# KEY_V0_01_160620.net
KiCad netlist of a schematic drawn in Altium Designer
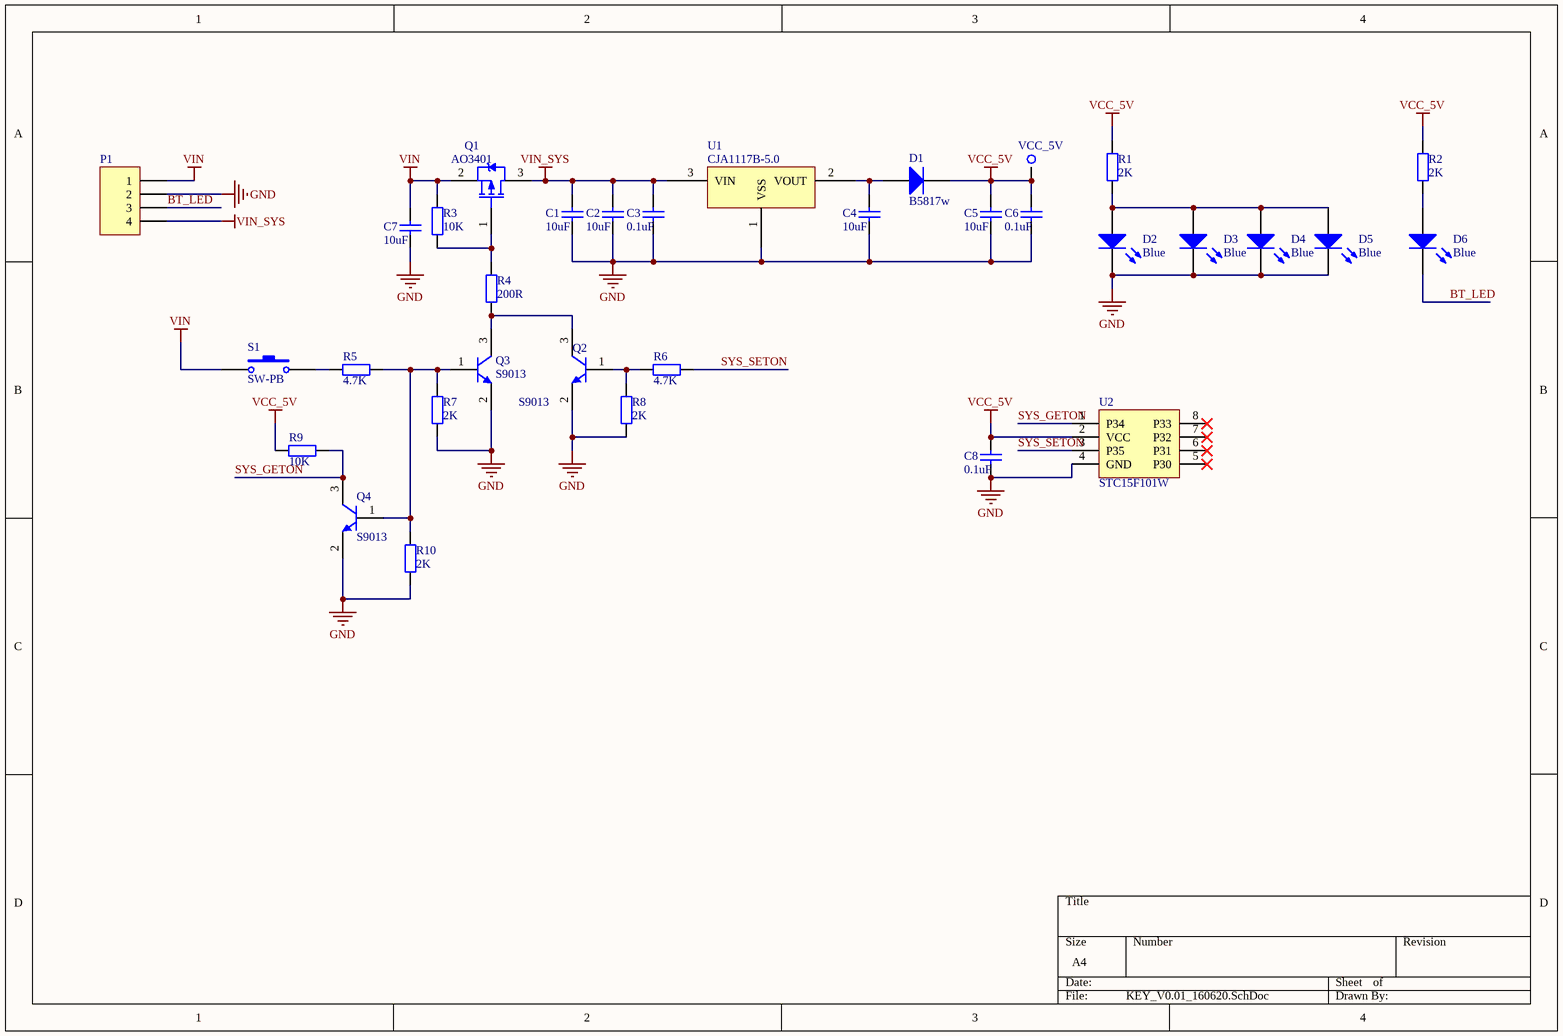
[diagram p0: KEY_V0.01_160620.SchDoc]

(export (version "E")
  (design (tool "Eeschema 10.0.6"))
  (components
    (comp (ref "C1")
      (value "10uF")
      (footprint "C0603")
      (description "三星 10uF 10% 16V C0603 X5R")
      (libsource (lib "Miscellaneous Devices") (part "Cap"))
    )
    (comp (ref "C2")
      (value "10uF")
      (footprint "C0603")
      (description "三星 10uF 10% 16V C0603 X5R")
      (libsource (lib "Miscellaneous Devices") (part "Cap"))
    )
    (comp (ref "C3")
      (value "0.1uF")
      (footprint "C0603")
      (description "三星 100nF 10% 25V C0603 X7R")
      (libsource (lib "Miscellaneous Devices") (part "Cap"))
    )
    (comp (ref "C4")
      (value "10uF")
      (footprint "C0603")
      (description "三星 10uF 10% 16V C0603 X5R")
      (libsource (lib "Miscellaneous Devices") (part "Cap"))
    )
    (comp (ref "C5")
      (value "10uF")
      (footprint "C0603")
      (description "三星 10uF 10% 16V C0603 X5R")
      (libsource (lib "Miscellaneous Devices") (part "Cap"))
    )
    (comp (ref "C6")
      (value "0.1uF")
      (footprint "C0603")
      (description "三星 100nF 10% 25V C0603 X7R")
      (libsource (lib "Miscellaneous Devices") (part "Cap"))
    )
    (comp (ref "C7")
      (value "10uF")
      (footprint "C0603")
      (description "三星 10uF 10% 16V C0603 X5R")
      (libsource (lib "Miscellaneous Devices") (part "Cap"))
    )
    (comp (ref "C8")
      (value "0.1uF")
      (footprint "C0603")
      (description "三星 100nF 10% 25V C0603 X7R")
      (libsource (lib "Miscellaneous Devices") (part "Cap"))
    )
    (comp (ref "D1")
      (value "B5817w")
      (footprint "SOD-123")
      (description "长电 B5817W SOD-123")
      (libsource (lib "Miscellaneous Devices") (part "Diode 1N4002"))
    )
    (comp (ref "D2")
      (value "Blue")
      (footprint "D0603")
      (description "蓝箭 蓝灯高亮 0603 Blue-LED")
      (libsource (lib "Miscellaneous Devices") (part "LED0"))
    )
    (comp (ref "D3")
      (value "Blue")
      (footprint "D0603")
      (description "蓝箭 蓝灯高亮 0603 Blue-LED")
      (libsource (lib "Miscellaneous Devices") (part "LED0"))
    )
    (comp (ref "D4")
      (value "Blue")
      (footprint "D0603")
      (description "蓝箭 蓝灯高亮 0603 Blue-LED")
      (libsource (lib "Miscellaneous Devices") (part "LED0"))
    )
    (comp (ref "D5")
      (value "Blue")
      (footprint "D0603")
      (description "蓝箭 蓝灯高亮 0603 Blue-LED")
      (libsource (lib "Miscellaneous Devices") (part "LED0"))
    )
    (comp (ref "D6")
      (value "Blue")
      (footprint "D0603")
      (description "蓝箭 蓝灯高亮 0603 Blue-LED")
      (libsource (lib "Miscellaneous Devices") (part "LED0"))
    )
    (comp (ref "P1")
      (value "Download_pad")
      (footprint "HEADER1X4/2.0MM_1")
      (description "AMP（国产仿制） AMP2.0mm-4Pin（板端） 间距2.00mm 卧插式 白色")
      (libsource (lib "Miscellaneous Connectors") (part "Header 4"))
    )
    (comp (ref "Q1") (value "AO3401") (footprint "SOT-23-3") (libsource (lib "makeblock") (part "PMOS")))
    (comp (ref "Q2") (value "S9013") (footprint "SOT-23") (libsource (lib "makeblock") (part "NPN_SMT")))
    (comp (ref "Q3") (value "S9013") (footprint "SOT-23") (libsource (lib "makeblock") (part "NPN_SMT")))
    (comp (ref "Q4") (value "S9013") (footprint "SOT-23") (libsource (lib "makeblock") (part "NPN_SMT")))
    (comp (ref "R1")
      (value "2K")
      (footprint "R0603")
      (description "国巨 2K 1% R0603")
      (libsource (lib "Miscellaneous Devices") (part "Res2"))
    )
    (comp (ref "R2")
      (value "2K")
      (footprint "R0603")
      (description "国巨 2K 1% R0603")
      (libsource (lib "") (part "Res2_2"))
    )
    (comp (ref "R3")
      (value "10K")
      (footprint "R0603")
      (description "国巨 10K 1% R0603")
      (libsource (lib "Miscellaneous Devices") (part "Res2"))
    )
    (comp (ref "R4")
      (value "200R")
      (footprint "R0603")
      (description "国巨 200R 1% R0603")
      (libsource (lib "Miscellaneous Devices") (part "Res2"))
    )
    (comp (ref "R5")
      (value "4.7K")
      (footprint "R0603")
      (description "国巨 4.7K 1% R0603")
      (libsource (lib "") (part "Res2_1"))
    )
    (comp (ref "R6")
      (value "4.7K")
      (footprint "R0603")
      (description "国巨 4.7K 1% R0603")
      (libsource (lib "") (part "Res2_1"))
    )
    (comp (ref "R7")
      (value "2K")
      (footprint "R0603")
      (description "国巨 2K 1% R0603")
      (libsource (lib "Miscellaneous Devices") (part "Res2"))
    )
    (comp (ref "R8")
      (value "2K")
      (footprint "R0603")
      (description "国巨 2K 1% R0603")
      (libsource (lib "Miscellaneous Devices") (part "Res2"))
    )
    (comp (ref "R9")
      (value "10K")
      (footprint "R0603")
      (description "国巨 10K 1% R0603")
      (libsource (lib "") (part "Res2_1"))
    )
    (comp (ref "R10")
      (value "2K")
      (footprint "R0603")
      (description "国巨 2K 1% R0603")
      (libsource (lib "Miscellaneous Devices") (part "Res2"))
    )
    (comp (ref "S1")
      (value "SW-PB")
      (footprint "SW-TS-021")
      (description "登鼎 3mm*6mm*2.5mm（长*宽*高） 贴片 白色按钮")
      (libsource (lib "Miscellaneous Devices") (part "SW-PB"))
    )
    (comp (ref "U1")
      (value "CJA1117B-5.0")
      (footprint "SOT-89-3L")
      (description "长电 三端稳压芯片 CJA1117B-3.3 3.3V 1A SOT-89-3L")
      (libsource (lib "Mylib") (part "XC6206"))
    )
    (comp (ref "U2")
      (value "STC15F101W")
      (footprint "SOP-8N")
      (description "宏晶 MCU STC15F101W SOP-8")
      (libsource (lib "makeblocK") (part "STC15F101W"))
    )
    (comp (ref "VCC_5V")
      (value "*")
      (footprint "Testpoint 1mm")
      (description "Testpoint")
      (libsource (lib "makeblocK") (part "Testpoint"))
    )
  )
  (nets
    (net (code "1") (name "/BT_LED") (class "Default")
      (node (ref "D6") (pin "2") (pinfunction "K_2") (pintype "passive"))
      (node (ref "P1") (pin "3") (pinfunction "3_3") (pintype "passive"))
    )
    (net (code "2") (name "/SYS_GETON") (class "Default")
      (node (ref "Q4") (pin "3") (pinfunction "C_3") (pintype "passive"))
      (node (ref "R9") (pin "1") (pinfunction "1_1") (pintype "passive"))
      (node (ref "U2") (pin "1") (pinfunction "P34_1") (pintype "passive"))
    )
    (net (code "3") (name "/SYS_SETON") (class "Default")
      (node (ref "R6") (pin "1") (pinfunction "1_1") (pintype "passive"))
      (node (ref "U2") (pin "3") (pinfunction "P35_3") (pintype "passive"))
    )
    (net (code "4") (name "GND") (class "Default")
      (node (ref "C1") (pin "2") (pinfunction "2_2") (pintype "passive"))
      (node (ref "C2") (pin "2") (pinfunction "2_2") (pintype "passive"))
      (node (ref "C3") (pin "2") (pinfunction "2_2") (pintype "passive"))
      (node (ref "C4") (pin "2") (pinfunction "2_2") (pintype "passive"))
      (node (ref "C5") (pin "2") (pinfunction "2_2") (pintype "passive"))
      (node (ref "C6") (pin "2") (pinfunction "2_2") (pintype "passive"))
      (node (ref "C7") (pin "2") (pinfunction "2_2") (pintype "passive"))
      (node (ref "C8") (pin "2") (pinfunction "2_2") (pintype "passive"))
      (node (ref "D2") (pin "2") (pinfunction "K_2") (pintype "passive"))
      (node (ref "D3") (pin "2") (pinfunction "K_2") (pintype "passive"))
      (node (ref "D4") (pin "2") (pinfunction "K_2") (pintype "passive"))
      (node (ref "D5") (pin "2") (pinfunction "K_2") (pintype "passive"))
      (node (ref "P1") (pin "2") (pinfunction "2_2") (pintype "passive"))
      (node (ref "Q2") (pin "2") (pinfunction "E_2") (pintype "passive"))
      (node (ref "Q3") (pin "2") (pinfunction "E_2") (pintype "passive"))
      (node (ref "Q4") (pin "2") (pinfunction "E_2") (pintype "passive"))
      (node (ref "R10") (pin "1") (pinfunction "1_1") (pintype "passive"))
      (node (ref "R7") (pin "1") (pinfunction "1_1") (pintype "passive"))
      (node (ref "R8") (pin "1") (pinfunction "1_1") (pintype "passive"))
      (node (ref "U1") (pin "1") (pinfunction "VSS_1") (pintype "passive"))
      (node (ref "U2") (pin "4") (pinfunction "GND_4") (pintype "passive"))
    )
    (net (code "5") (name "Net-(D1-A)") (class "Default")
      (node (ref "C4") (pin "1") (pinfunction "1_1") (pintype "passive"))
      (node (ref "D1") (pin "1") (pinfunction "A_1") (pintype "passive"))
      (node (ref "U1") (pin "2") (pinfunction "VOUT_2") (pintype "passive"))
    )
    (net (code "6") (name "Net-(D2-A)") (class "Default")
      (node (ref "D2") (pin "1") (pinfunction "A_1") (pintype "passive"))
      (node (ref "D3") (pin "1") (pinfunction "A_1") (pintype "passive"))
      (node (ref "D4") (pin "1") (pinfunction "A_1") (pintype "passive"))
      (node (ref "D5") (pin "1") (pinfunction "A_1") (pintype "passive"))
      (node (ref "R1") (pin "1") (pinfunction "1_1") (pintype "passive"))
    )
    (net (code "7") (name "Net-(D6-A)") (class "Default")
      (node (ref "D6") (pin "1") (pinfunction "A_1") (pintype "passive"))
      (node (ref "R2") (pin "2") (pinfunction "2_2") (pintype "passive"))
    )
    (net (code "8") (name "Net-(Q1-G)") (class "Default")
      (node (ref "Q1") (pin "1") (pinfunction "G_1") (pintype "passive"))
      (node (ref "R3") (pin "1") (pinfunction "1_1") (pintype "passive"))
      (node (ref "R4") (pin "2") (pinfunction "2_2") (pintype "passive"))
    )
    (net (code "9") (name "Net-(Q2-B)") (class "Default")
      (node (ref "Q2") (pin "1") (pinfunction "B_1") (pintype "passive"))
      (node (ref "R6") (pin "2") (pinfunction "2_2") (pintype "passive"))
      (node (ref "R8") (pin "2") (pinfunction "2_2") (pintype "passive"))
    )
    (net (code "10") (name "Net-(Q2-C)") (class "Default")
      (node (ref "Q2") (pin "3") (pinfunction "C_3") (pintype "passive"))
      (node (ref "Q3") (pin "3") (pinfunction "C_3") (pintype "passive"))
      (node (ref "R4") (pin "1") (pinfunction "1_1") (pintype "passive"))
    )
    (net (code "11") (name "Net-(Q3-B)") (class "Default")
      (node (ref "Q3") (pin "1") (pinfunction "B_1") (pintype "passive"))
      (node (ref "Q4") (pin "1") (pinfunction "B_1") (pintype "passive"))
      (node (ref "R10") (pin "2") (pinfunction "2_2") (pintype "passive"))
      (node (ref "R5") (pin "1") (pinfunction "1_1") (pintype "passive"))
      (node (ref "R7") (pin "2") (pinfunction "2_2") (pintype "passive"))
    )
    (net (code "12") (name "Net-(R5-Pad2)") (class "Default")
      (node (ref "R5") (pin "2") (pinfunction "2_2") (pintype "passive"))
      (node (ref "S1") (pin "2") (pinfunction "2_2") (pintype "passive"))
    )
    (net (code "13") (name "VCC_5V") (class "Default")
      (node (ref "C5") (pin "1") (pinfunction "1_1") (pintype "passive"))
      (node (ref "C6") (pin "1") (pinfunction "1_1") (pintype "passive"))
      (node (ref "C8") (pin "1") (pinfunction "1_1") (pintype "passive"))
      (node (ref "D1") (pin "2") (pinfunction "K_2") (pintype "passive"))
      (node (ref "R1") (pin "2") (pinfunction "2_2") (pintype "passive"))
      (node (ref "R2") (pin "1") (pinfunction "1_1") (pintype "passive"))
      (node (ref "R9") (pin "2") (pinfunction "2_2") (pintype "passive"))
      (node (ref "U2") (pin "2") (pinfunction "VCC_2") (pintype "passive"))
      (node (ref "VCC_5V") (pin "1") (pinfunction "1_1") (pintype "passive"))
    )
    (net (code "14") (name "VIN") (class "Default")
      (node (ref "C7") (pin "1") (pinfunction "1_1") (pintype "passive"))
      (node (ref "P1") (pin "1") (pinfunction "1_1") (pintype "passive"))
      (node (ref "Q1") (pin "2") (pinfunction "S_2") (pintype "passive"))
      (node (ref "R3") (pin "2") (pinfunction "2_2") (pintype "passive"))
      (node (ref "S1") (pin "1") (pinfunction "1_1") (pintype "passive"))
    )
    (net (code "15") (name "VIN_SYS") (class "Default")
      (node (ref "C1") (pin "1") (pinfunction "1_1") (pintype "passive"))
      (node (ref "C2") (pin "1") (pinfunction "1_1") (pintype "passive"))
      (node (ref "C3") (pin "1") (pinfunction "1_1") (pintype "passive"))
      (node (ref "P1") (pin "4") (pinfunction "4_4") (pintype "passive"))
      (node (ref "Q1") (pin "3") (pinfunction "D_3") (pintype "passive"))
      (node (ref "U1") (pin "3") (pinfunction "VIN_3") (pintype "passive"))
    )
    (net (code "16") (name "unconnected-(U2-P30-Pad5)") (class "Default")
      (node (ref "U2") (pin "5") (pinfunction "P30_5") (pintype "passive+no_connect"))
    )
    (net (code "17") (name "unconnected-(U2-P31-Pad6)") (class "Default")
      (node (ref "U2") (pin "6") (pinfunction "P31_6") (pintype "passive+no_connect"))
    )
    (net (code "18") (name "unconnected-(U2-P32-Pad7)") (class "Default")
      (node (ref "U2") (pin "7") (pinfunction "P32_7") (pintype "passive+no_connect"))
    )
    (net (code "19") (name "unconnected-(U2-P33-Pad8)") (class "Default")
      (node (ref "U2") (pin "8") (pinfunction "P33_8") (pintype "passive+no_connect"))
    )
  )
)
